# PSIO_Switchboard_PU-22_v1.net
KiCad netlist of a schematic drawn in EAGLE
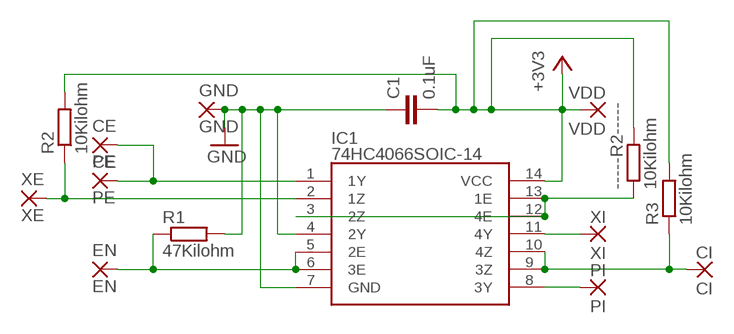
[diagram p0: schematic, sheet 1]

(export (version "E")
  (design (tool "Eeschema 10.0.6"))
  (components
    (comp (ref "-----R2-----")
      (value "10Kilohm")
      (footprint "eagle-import:R0805")
      (libsource (lib "eagle-import") (part "RESISTORSR0805"))
    )
    (comp (ref "C1")
      (value "0.1uF")
      (footprint "eagle-import:C0805")
      (libsource (lib "eagle-import") (part "CAPACITORSC0805"))
    )
    (comp (ref "CE")
      (value "CE")
      (footprint "eagle-import:CIRCLE-2X2")
      (libsource (lib "eagle-import") (part "PADSCIRCLE-2X2"))
    )
    (comp (ref "CI")
      (value "CI")
      (footprint "eagle-import:CIRCLE-2X2")
      (libsource (lib "eagle-import") (part "PADSCIRCLE-2X2"))
    )
    (comp (ref "EN")
      (value "EN")
      (footprint "eagle-import:CIRCLE-2X2")
      (libsource (lib "eagle-import") (part "PADSCIRCLE-2X2"))
    )
    (comp (ref "GND")
      (value "GND")
      (footprint "eagle-import:CIRCLE-2X2")
      (libsource (lib "eagle-import") (part "PADSCIRCLE-2X2"))
    )
    (comp (ref "IC1")
      (value "74HC4066SOIC-14")
      (footprint "eagle-import:SOIC-14")
      (libsource (lib "eagle-import") (part "74HC4066SOIC-14"))
    )
    (comp (ref "PE")
      (value "PE")
      (footprint "eagle-import:CIRCLE-2X2")
      (libsource (lib "eagle-import") (part "PADSCIRCLE-2X2"))
    )
    (comp (ref "PI")
      (value "PI")
      (footprint "eagle-import:CIRCLE-2X2")
      (libsource (lib "eagle-import") (part "PADSCIRCLE-2X2"))
    )
    (comp (ref "R1")
      (value "47Kilohm")
      (footprint "eagle-import:R0805")
      (libsource (lib "eagle-import") (part "RESISTORSR0805"))
    )
    (comp (ref "R2")
      (value "10Kilohm")
      (footprint "eagle-import:R0805")
      (libsource (lib "eagle-import") (part "RESISTORSR0805"))
    )
    (comp (ref "R3")
      (value "10Kilohm")
      (footprint "eagle-import:R0805")
      (libsource (lib "eagle-import") (part "RESISTORSR0805"))
    )
    (comp (ref "VDD")
      (value "VDD")
      (footprint "eagle-import:CIRCLE-2X2")
      (libsource (lib "eagle-import") (part "PADSCIRCLE-2X2"))
    )
    (comp (ref "XE")
      (value "XE")
      (footprint "eagle-import:CIRCLE-2X2")
      (libsource (lib "eagle-import") (part "PADSCIRCLE-2X2"))
    )
    (comp (ref "XI")
      (value "XI")
      (footprint "eagle-import:CIRCLE-2X2")
      (libsource (lib "eagle-import") (part "PADSCIRCLE-2X2"))
    )
  )
  (nets
    (net (code "1") (name "+3V3") (class "Default")
      (node (ref "-----R2-----") (pin "2") (pinfunction "2_2") (pintype "passive"))
      (node (ref "C1") (pin "2") (pinfunction "2_2") (pintype "passive"))
      (node (ref "IC1") (pin "14") (pinfunction "VCC_14") (pintype "bidirectional"))
      (node (ref "R2") (pin "2") (pinfunction "2_2") (pintype "passive"))
      (node (ref "R3") (pin "2") (pinfunction "2_2") (pintype "passive"))
      (node (ref "VDD") (pin "1") (pinfunction "P_1") (pintype "passive"))
    )
    (net (code "2") (name "GND") (class "Default")
      (node (ref "C1") (pin "1") (pinfunction "1_1") (pintype "passive"))
      (node (ref "GND") (pin "1") (pinfunction "P_1") (pintype "passive"))
      (node (ref "IC1") (pin "4") (pinfunction "2Y_4") (pintype "bidirectional"))
      (node (ref "IC1") (pin "7") (pinfunction "GND_7") (pintype "bidirectional"))
      (node (ref "R1") (pin "2") (pinfunction "2_2") (pintype "passive"))
    )
    (net (code "3") (name "Net-(CE-P)") (class "Default")
      (node (ref "CE") (pin "1") (pinfunction "P_1") (pintype "passive"))
      (node (ref "IC1") (pin "1") (pinfunction "1Y_1") (pintype "bidirectional"))
      (node (ref "PE") (pin "1") (pinfunction "P_1") (pintype "passive"))
    )
    (net (code "4") (name "Net-(CI-P)") (class "Default")
      (node (ref "CI") (pin "1") (pinfunction "P_1") (pintype "passive"))
      (node (ref "IC1") (pin "10") (pinfunction "4Z_10") (pintype "bidirectional"))
      (node (ref "IC1") (pin "9") (pinfunction "3Z_9") (pintype "bidirectional"))
      (node (ref "R3") (pin "1") (pinfunction "1_1") (pintype "passive"))
    )
    (net (code "5") (name "Net-(EN-P)") (class "Default")
      (node (ref "EN") (pin "1") (pinfunction "P_1") (pintype "passive"))
      (node (ref "IC1") (pin "5") (pinfunction "2E_5") (pintype "bidirectional"))
      (node (ref "IC1") (pin "6") (pinfunction "3E_6") (pintype "bidirectional"))
      (node (ref "R1") (pin "1") (pinfunction "1_1") (pintype "passive"))
    )
    (net (code "6") (name "Net-(IC1-1E)") (class "Default")
      (node (ref "-----R2-----") (pin "1") (pinfunction "1_1") (pintype "passive"))
      (node (ref "IC1") (pin "12") (pinfunction "4E_12") (pintype "bidirectional"))
      (node (ref "IC1") (pin "13") (pinfunction "1E_13") (pintype "bidirectional"))
      (node (ref "IC1") (pin "3") (pinfunction "2Z_3") (pintype "bidirectional"))
    )
    (net (code "7") (name "Net-(IC1-1Z)") (class "Default")
      (node (ref "IC1") (pin "2") (pinfunction "1Z_2") (pintype "bidirectional"))
      (node (ref "R2") (pin "1") (pinfunction "1_1") (pintype "passive"))
      (node (ref "XE") (pin "1") (pinfunction "P_1") (pintype "passive"))
    )
    (net (code "8") (name "Net-(IC1-3Y)") (class "Default")
      (node (ref "IC1") (pin "8") (pinfunction "3Y_8") (pintype "bidirectional"))
      (node (ref "PI") (pin "1") (pinfunction "P_1") (pintype "passive"))
    )
    (net (code "9") (name "Net-(IC1-4Y)") (class "Default")
      (node (ref "IC1") (pin "11") (pinfunction "4Y_11") (pintype "bidirectional"))
      (node (ref "XI") (pin "1") (pinfunction "P_1") (pintype "passive"))
    )
  )
)
